# OutputModule.net
KiCad netlist of a schematic drawn in Altium Designer
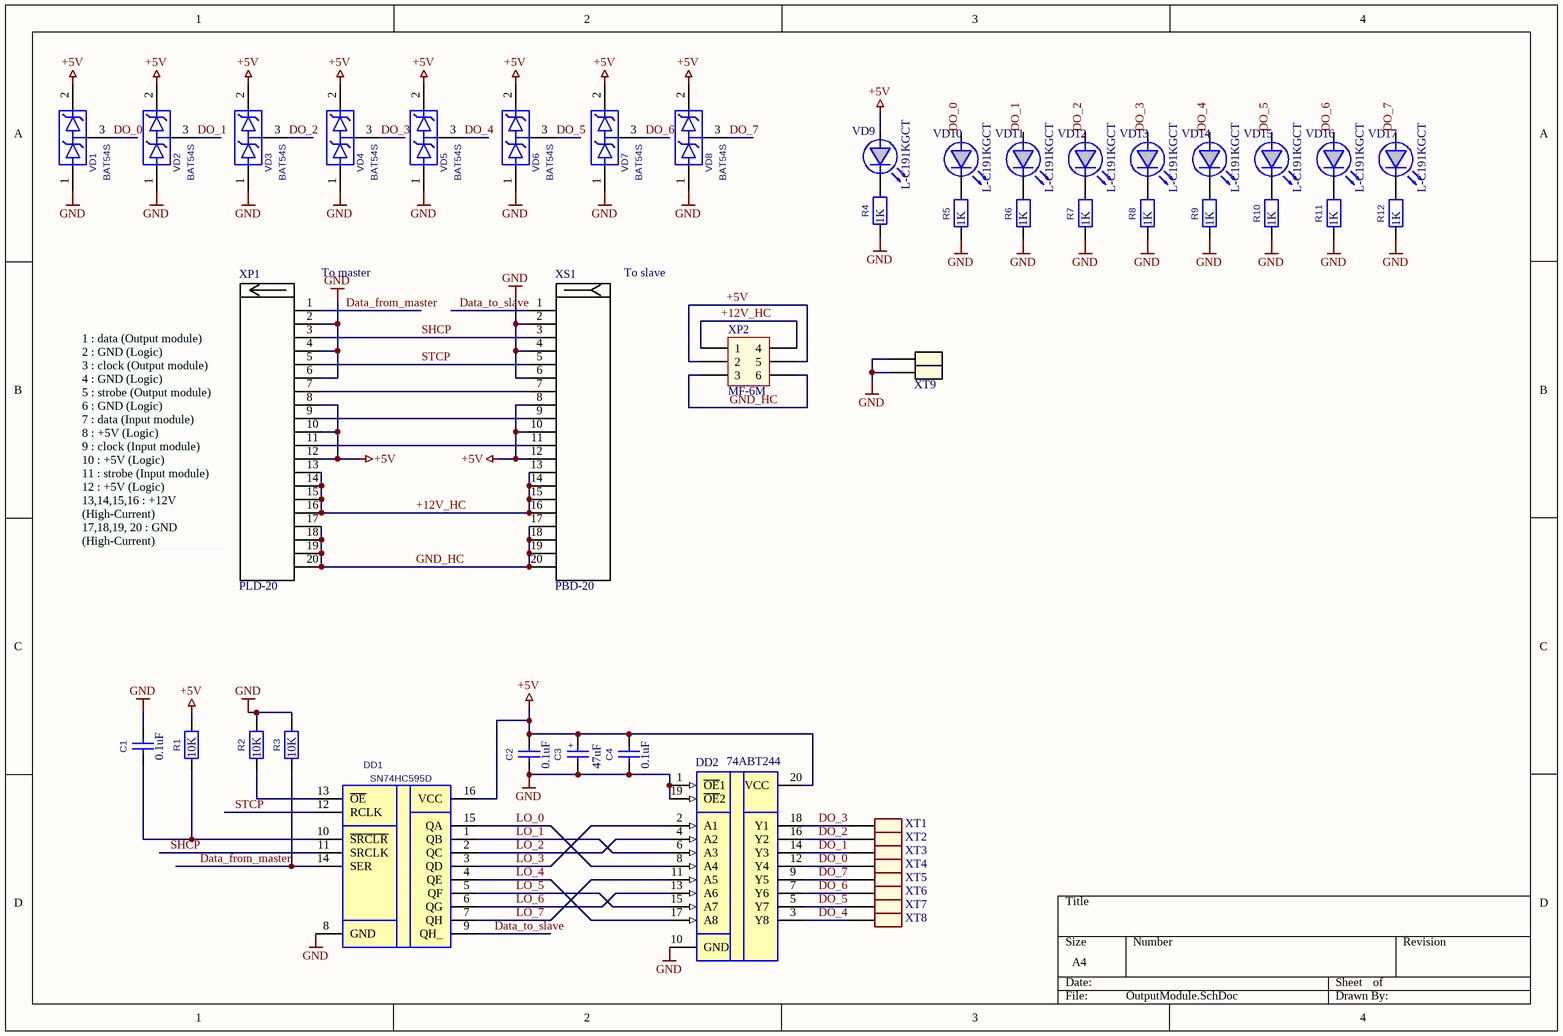
[diagram p0: OutputModule.SchDoc]

(export (version "E")
  (design (tool "Eeschema 10.0.6"))
  (components
    (comp (ref "C1")
      (value "0.1uF")
      (footprint "C-1608[0603]")
      (description "C-0603")
      (libsource (lib "Altium-RC") (part "C-0603"))
    )
    (comp (ref "C2")
      (value "0.1uF")
      (footprint "C-1608[0603]")
      (description "C-0603")
      (libsource (lib "Altium-RC") (part "C-0603"))
    )
    (comp (ref "C3")
      (value "47uF")
      (footprint "C-CASE")
      (description "C-CCASE")
      (libsource (lib "Altium-RC") (part "C-CCASE"))
    )
    (comp (ref "C4")
      (value "0.1uF")
      (footprint "C-1608[0603]")
      (description "C-0603")
      (libsource (lib "Altium-RC") (part "C-0603"))
    )
    (comp (ref "DD1")
      (value "SN74HC595D")
      (footprint "SO-G16")
      (libsource (lib "Altium-IC") (part "SN74HC595D"))
    )
    (comp (ref "DD2")
      (value "74ABT244")
      (footprint "TSSOP20")
      (description "Octal Buffer/Driver with 3-State Outputs")
      (libsource (lib "Altium-IC") (part "SN74LVC244APW"))
    )
    (comp (ref "R1")
      (value "10K")
      (footprint "R-1608[0603]")
      (description "R-0603")
      (libsource (lib "Altium-RC") (part "R-0603"))
    )
    (comp (ref "R2")
      (value "10K")
      (footprint "R-1608[0603]")
      (description "R-0603")
      (libsource (lib "Altium-RC") (part "R-0603"))
    )
    (comp (ref "R3")
      (value "10K")
      (footprint "R-1608[0603]")
      (description "R-0603")
      (libsource (lib "Altium-RC") (part "R-0603"))
    )
    (comp (ref "R4")
      (value "1K")
      (footprint "R-1608[0603]")
      (description "R-0603")
      (libsource (lib "Altium-RC") (part "R-0603"))
    )
    (comp (ref "R5")
      (value "1K")
      (footprint "R-1608[0603]")
      (description "R-0603")
      (libsource (lib "Altium-RC") (part "R-0603"))
    )
    (comp (ref "R6")
      (value "1K")
      (footprint "R-1608[0603]")
      (description "R-0603")
      (libsource (lib "Altium-RC") (part "R-0603"))
    )
    (comp (ref "R7")
      (value "1K")
      (footprint "R-1608[0603]")
      (description "R-0603")
      (libsource (lib "Altium-RC") (part "R-0603"))
    )
    (comp (ref "R8")
      (value "1K")
      (footprint "R-1608[0603]")
      (description "R-0603")
      (libsource (lib "Altium-RC") (part "R-0603"))
    )
    (comp (ref "R9")
      (value "1K")
      (footprint "R-1608[0603]")
      (description "R-0603")
      (libsource (lib "Altium-RC") (part "R-0603"))
    )
    (comp (ref "R10")
      (value "1K")
      (footprint "R-1608[0603]")
      (description "R-0603")
      (libsource (lib "Altium-RC") (part "R-0603"))
    )
    (comp (ref "R11")
      (value "1K")
      (footprint "R-1608[0603]")
      (description "R-0603")
      (libsource (lib "Altium-RC") (part "R-0603"))
    )
    (comp (ref "R12")
      (value "1K")
      (footprint "R-1608[0603]")
      (description "R-0603")
      (libsource (lib "Altium-RC") (part "R-0603"))
    )
    (comp (ref "VD1")
      (value "BAT54S")
      (footprint "SOT-23")
      (description "Schottky barrier (double) diodes")
      (libsource (lib "Altium-RECT") (part "BAT54S"))
    )
    (comp (ref "VD2")
      (value "BAT54S")
      (footprint "SOT-23")
      (description "Schottky barrier (double) diodes")
      (libsource (lib "Altium-RECT") (part "BAT54S"))
    )
    (comp (ref "VD3")
      (value "BAT54S")
      (footprint "SOT-23")
      (description "Schottky barrier (double) diodes")
      (libsource (lib "Altium-RECT") (part "BAT54S"))
    )
    (comp (ref "VD4")
      (value "BAT54S")
      (footprint "SOT-23")
      (description "Schottky barrier (double) diodes")
      (libsource (lib "Altium-RECT") (part "BAT54S"))
    )
    (comp (ref "VD5")
      (value "BAT54S")
      (footprint "SOT-23")
      (description "Schottky barrier (double) diodes")
      (libsource (lib "Altium-RECT") (part "BAT54S"))
    )
    (comp (ref "VD6")
      (value "BAT54S")
      (footprint "SOT-23")
      (description "Schottky barrier (double) diodes")
      (libsource (lib "Altium-RECT") (part "BAT54S"))
    )
    (comp (ref "VD7")
      (value "BAT54S")
      (footprint "SOT-23")
      (description "Schottky barrier (double) diodes")
      (libsource (lib "Altium-RECT") (part "BAT54S"))
    )
    (comp (ref "VD8")
      (value "BAT54S")
      (footprint "SOT-23")
      (description "Schottky barrier (double) diodes")
      (libsource (lib "Altium-RECT") (part "BAT54S"))
    )
    (comp (ref "VD9")
      (value "L-C191KGCT")
      (footprint "LED-0603")
      (description "0603 Green Led")
      (libsource (lib "Altium-OPTO") (part "L-C191KGCT"))
    )
    (comp (ref "VD10")
      (value "L-C191KGCT")
      (footprint "LED-0603")
      (description "0603 Green Led")
      (libsource (lib "Altium-OPTO") (part "L-C191KGCT"))
    )
    (comp (ref "VD11")
      (value "L-C191KGCT")
      (footprint "LED-0603")
      (description "0603 Green Led")
      (libsource (lib "Altium-OPTO") (part "L-C191KGCT"))
    )
    (comp (ref "VD12")
      (value "L-C191KGCT")
      (footprint "LED-0603")
      (description "0603 Green Led")
      (libsource (lib "Altium-OPTO") (part "L-C191KGCT"))
    )
    (comp (ref "VD13")
      (value "L-C191KGCT")
      (footprint "LED-0603")
      (description "0603 Green Led")
      (libsource (lib "Altium-OPTO") (part "L-C191KGCT"))
    )
    (comp (ref "VD14")
      (value "L-C191KGCT")
      (footprint "LED-0603")
      (description "0603 Green Led")
      (libsource (lib "Altium-OPTO") (part "L-C191KGCT"))
    )
    (comp (ref "VD15")
      (value "L-C191KGCT")
      (footprint "LED-0603")
      (description "0603 Green Led")
      (libsource (lib "Altium-OPTO") (part "L-C191KGCT"))
    )
    (comp (ref "VD16")
      (value "L-C191KGCT")
      (footprint "LED-0603")
      (description "0603 Green Led")
      (libsource (lib "Altium-OPTO") (part "L-C191KGCT"))
    )
    (comp (ref "VD17")
      (value "L-C191KGCT")
      (footprint "LED-0603")
      (description "0603 Green Led")
      (libsource (lib "Altium-OPTO") (part "L-C191KGCT"))
    )
    (comp (ref "XP1")
      (value "PLD-20")
      (footprint "PLD-20 ROT")
      (description "20 pin, 2 row, MALE connector")
      (libsource (lib "Altium-CONN") (part "PLD-20"))
    )
    (comp (ref "XP2")
      (value "MF-6M")
      (footprint "MF-6M")
      (description "Molex Male connector")
      (libsource (lib "Altium-CONN") (part "MF-6M"))
    )
    (comp (ref "XS1")
      (value "PBD-20")
      (footprint "PBD-20 Rot")
      (description "2.54mm, 20 pin FEMALE connector")
      (libsource (lib "Altium-CONN") (part "PBD-20"))
    )
    (comp (ref "XT1")
      (value "DG141V-01P")
      (footprint "DG141V-01P (XY123R)")
      (description "Клеммник нажимной 2.54мм")
      (libsource (lib "Altium-CONN") (part "DG141V-01P"))
    )
    (comp (ref "XT2")
      (value "DG141V-01P")
      (footprint "DG141V-01P (XY123R)")
      (description "Клеммник нажимной 2.54мм")
      (libsource (lib "Altium-CONN") (part "DG141V-01P"))
    )
    (comp (ref "XT3")
      (value "DG141V-01P")
      (footprint "DG141V-01P (XY123R)")
      (description "Клеммник нажимной 2.54мм")
      (libsource (lib "Altium-CONN") (part "DG141V-01P"))
    )
    (comp (ref "XT4")
      (value "DG141V-01P")
      (footprint "DG141V-01P (XY123R)")
      (description "Клеммник нажимной 2.54мм")
      (libsource (lib "Altium-CONN") (part "DG141V-01P"))
    )
    (comp (ref "XT5")
      (value "DG141V-01P")
      (footprint "DG141V-01P (XY123R)")
      (description "Клеммник нажимной 2.54мм")
      (libsource (lib "Altium-CONN") (part "DG141V-01P"))
    )
    (comp (ref "XT6")
      (value "DG141V-01P")
      (footprint "DG141V-01P (XY123R)")
      (description "Клеммник нажимной 2.54мм")
      (libsource (lib "Altium-CONN") (part "DG141V-01P"))
    )
    (comp (ref "XT7")
      (value "DG141V-01P")
      (footprint "DG141V-01P (XY123R)")
      (description "Клеммник нажимной 2.54мм")
      (libsource (lib "Altium-CONN") (part "DG141V-01P"))
    )
    (comp (ref "XT8")
      (value "DG141V-01P")
      (footprint "DG141V-01P (XY123R)")
      (description "Клеммник нажимной 2.54мм")
      (libsource (lib "Altium-CONN") (part "DG141V-01P"))
    )
    (comp (ref "XT9")
      (value "1-1776244-0 (TYCO)")
      (footprint "1-1776244-0")
      (description "Винтовой клеммник 5.0мм")
      (libsource (lib "Altium-CONN") (part "1-1776244-0 (TYCO)"))
    )
  )
  (nets
    (net (code "1") (name "+5V") (class "Default")
      (node (ref "C2") (pin "1") (pintype "passive"))
      (node (ref "C3") (pin "1") (pinfunction "+_1") (pintype "passive"))
      (node (ref "C4") (pin "1") (pintype "passive"))
      (node (ref "DD1") (pin "16") (pinfunction "VCC_16") (pintype "passive"))
      (node (ref "DD2") (pin "20") (pinfunction "VCC_20") (pintype "power_in"))
      (node (ref "R1") (pin "2") (pinfunction "2_2") (pintype "passive"))
      (node (ref "VD1") (pin "2") (pinfunction "c_2") (pintype "passive"))
      (node (ref "VD2") (pin "2") (pinfunction "c_2") (pintype "passive"))
      (node (ref "VD3") (pin "2") (pinfunction "c_2") (pintype "passive"))
      (node (ref "VD4") (pin "2") (pinfunction "c_2") (pintype "passive"))
      (node (ref "VD5") (pin "2") (pinfunction "c_2") (pintype "passive"))
      (node (ref "VD6") (pin "2") (pinfunction "c_2") (pintype "passive"))
      (node (ref "VD7") (pin "2") (pinfunction "c_2") (pintype "passive"))
      (node (ref "VD8") (pin "2") (pinfunction "c_2") (pintype "passive"))
      (node (ref "VD9") (pin "2") (pinfunction "A_2") (pintype "passive"))
      (node (ref "XP1") (pin "10") (pintype "passive"))
      (node (ref "XP1") (pin "12") (pintype "passive"))
      (node (ref "XP1") (pin "8") (pintype "passive"))
      (node (ref "XP2") (pin "2") (pinfunction "2_2") (pintype "passive"))
      (node (ref "XP2") (pin "5") (pinfunction "5_5") (pintype "passive"))
      (node (ref "XS1") (pin "10") (pintype "passive"))
      (node (ref "XS1") (pin "12") (pintype "passive"))
      (node (ref "XS1") (pin "8") (pintype "passive"))
    )
    (net (code "2") (name "/+12V_HC") (class "Default")
      (node (ref "XP1") (pin "13") (pintype "passive"))
      (node (ref "XP1") (pin "14") (pintype "passive"))
      (node (ref "XP1") (pin "15") (pintype "passive"))
      (node (ref "XP1") (pin "16") (pintype "passive"))
      (node (ref "XP2") (pin "1") (pinfunction "1_1") (pintype "passive"))
      (node (ref "XP2") (pin "4") (pinfunction "4_4") (pintype "passive"))
      (node (ref "XS1") (pin "13") (pintype "passive"))
      (node (ref "XS1") (pin "14") (pintype "passive"))
      (node (ref "XS1") (pin "15") (pintype "passive"))
      (node (ref "XS1") (pin "16") (pintype "passive"))
    )
    (net (code "3") (name "/DO_0") (class "Default")
      (node (ref "DD2") (pin "12") (pinfunction "Y4_12") (pintype "tri_state"))
      (node (ref "VD1") (pin "3") (pinfunction "ka_3") (pintype "passive"))
      (node (ref "VD10") (pin "2") (pinfunction "A_2") (pintype "passive"))
      (node (ref "XT4") (pin "1") (pintype "passive"))
    )
    (net (code "4") (name "/DO_1") (class "Default")
      (node (ref "DD2") (pin "14") (pinfunction "Y3_14") (pintype "tri_state"))
      (node (ref "VD11") (pin "2") (pinfunction "A_2") (pintype "passive"))
      (node (ref "VD2") (pin "3") (pinfunction "ka_3") (pintype "passive"))
      (node (ref "XT3") (pin "1") (pintype "passive"))
    )
    (net (code "5") (name "/DO_2") (class "Default")
      (node (ref "DD2") (pin "16") (pinfunction "Y2_16") (pintype "tri_state"))
      (node (ref "VD12") (pin "2") (pinfunction "A_2") (pintype "passive"))
      (node (ref "VD3") (pin "3") (pinfunction "ka_3") (pintype "passive"))
      (node (ref "XT2") (pin "1") (pintype "passive"))
    )
    (net (code "6") (name "/DO_3") (class "Default")
      (node (ref "DD2") (pin "18") (pinfunction "Y1_18") (pintype "tri_state"))
      (node (ref "VD13") (pin "2") (pinfunction "A_2") (pintype "passive"))
      (node (ref "VD4") (pin "3") (pinfunction "ka_3") (pintype "passive"))
      (node (ref "XT1") (pin "1") (pintype "passive"))
    )
    (net (code "7") (name "/DO_4") (class "Default")
      (node (ref "DD2") (pin "3") (pinfunction "Y8_3") (pintype "tri_state"))
      (node (ref "VD14") (pin "2") (pinfunction "A_2") (pintype "passive"))
      (node (ref "VD5") (pin "3") (pinfunction "ka_3") (pintype "passive"))
      (node (ref "XT8") (pin "1") (pintype "passive"))
    )
    (net (code "8") (name "/DO_5") (class "Default")
      (node (ref "DD2") (pin "5") (pinfunction "Y7_5") (pintype "tri_state"))
      (node (ref "VD15") (pin "2") (pinfunction "A_2") (pintype "passive"))
      (node (ref "VD6") (pin "3") (pinfunction "ka_3") (pintype "passive"))
      (node (ref "XT7") (pin "1") (pintype "passive"))
    )
    (net (code "9") (name "/DO_6") (class "Default")
      (node (ref "DD2") (pin "7") (pinfunction "Y6_7") (pintype "tri_state"))
      (node (ref "VD16") (pin "2") (pinfunction "A_2") (pintype "passive"))
      (node (ref "VD7") (pin "3") (pinfunction "ka_3") (pintype "passive"))
      (node (ref "XT6") (pin "1") (pintype "passive"))
    )
    (net (code "10") (name "/DO_7") (class "Default")
      (node (ref "DD2") (pin "9") (pinfunction "Y5_9") (pintype "tri_state"))
      (node (ref "VD17") (pin "2") (pinfunction "A_2") (pintype "passive"))
      (node (ref "VD8") (pin "3") (pinfunction "ka_3") (pintype "passive"))
      (node (ref "XT5") (pin "1") (pintype "passive"))
    )
    (net (code "11") (name "/Data_from_master") (class "Default")
      (node (ref "DD1") (pin "14") (pinfunction "SER_14") (pintype "passive"))
      (node (ref "R3") (pin "1") (pinfunction "1_1") (pintype "passive"))
      (node (ref "XP1") (pin "1") (pintype "passive"))
    )
    (net (code "12") (name "/Data_to_slave") (class "Default")
      (node (ref "DD1") (pin "9") (pinfunction "QH__9") (pintype "passive"))
      (node (ref "XS1") (pin "1") (pintype "passive"))
    )
    (net (code "13") (name "/GND_HC") (class "Default")
      (node (ref "XP1") (pin "17") (pintype "passive"))
      (node (ref "XP1") (pin "18") (pintype "passive"))
      (node (ref "XP1") (pin "19") (pintype "passive"))
      (node (ref "XP1") (pin "20") (pintype "passive"))
      (node (ref "XP2") (pin "3") (pinfunction "3_3") (pintype "passive"))
      (node (ref "XP2") (pin "6") (pinfunction "6_6") (pintype "passive"))
      (node (ref "XS1") (pin "17") (pintype "passive"))
      (node (ref "XS1") (pin "18") (pintype "passive"))
      (node (ref "XS1") (pin "19") (pintype "passive"))
      (node (ref "XS1") (pin "20") (pintype "passive"))
    )
    (net (code "14") (name "/LO_0") (class "Default")
      (node (ref "DD1") (pin "15") (pinfunction "QA_15") (pintype "passive"))
      (node (ref "DD2") (pin "8") (pinfunction "A4_8") (pintype "input"))
    )
    (net (code "15") (name "/LO_1") (class "Default")
      (node (ref "DD1") (pin "1") (pinfunction "QB_1") (pintype "passive"))
      (node (ref "DD2") (pin "6") (pinfunction "A3_6") (pintype "input"))
    )
    (net (code "16") (name "/LO_2") (class "Default")
      (node (ref "DD1") (pin "2") (pinfunction "QC_2") (pintype "passive"))
      (node (ref "DD2") (pin "4") (pinfunction "A2_4") (pintype "input"))
    )
    (net (code "17") (name "/LO_3") (class "Default")
      (node (ref "DD1") (pin "3") (pinfunction "QD_3") (pintype "passive"))
      (node (ref "DD2") (pin "2") (pinfunction "A1_2") (pintype "input"))
    )
    (net (code "18") (name "/LO_4") (class "Default")
      (node (ref "DD1") (pin "4") (pinfunction "QE_4") (pintype "passive"))
      (node (ref "DD2") (pin "17") (pinfunction "A8_17") (pintype "input"))
    )
    (net (code "19") (name "/LO_5") (class "Default")
      (node (ref "DD1") (pin "5") (pinfunction "QF_5") (pintype "passive"))
      (node (ref "DD2") (pin "15") (pinfunction "A7_15") (pintype "input"))
    )
    (net (code "20") (name "/LO_6") (class "Default")
      (node (ref "DD1") (pin "6") (pinfunction "QG_6") (pintype "passive"))
      (node (ref "DD2") (pin "13") (pinfunction "A6_13") (pintype "input"))
    )
    (net (code "21") (name "/LO_7") (class "Default")
      (node (ref "DD1") (pin "7") (pinfunction "QH_7") (pintype "passive"))
      (node (ref "DD2") (pin "11") (pinfunction "A5_11") (pintype "input"))
    )
    (net (code "22") (name "/SHCP") (class "Default")
      (node (ref "DD1") (pin "11") (pinfunction "SRCLK_11") (pintype "passive"))
      (node (ref "XP1") (pin "3") (pintype "passive"))
      (node (ref "XS1") (pin "3") (pintype "passive"))
    )
    (net (code "23") (name "/STCP") (class "Default")
      (node (ref "DD1") (pin "12") (pinfunction "RCLK_12") (pintype "passive"))
      (node (ref "XP1") (pin "5") (pintype "passive"))
      (node (ref "XS1") (pin "5") (pintype "passive"))
    )
    (net (code "24") (name "GND") (class "Default")
      (node (ref "C1") (pin "1") (pintype "passive"))
      (node (ref "C2") (pin "2") (pintype "passive"))
      (node (ref "C3") (pin "2") (pinfunction "-_2") (pintype "passive"))
      (node (ref "C4") (pin "2") (pintype "passive"))
      (node (ref "DD1") (pin "8") (pinfunction "GND_8") (pintype "passive"))
      (node (ref "DD2") (pin "1") (pinfunction "~{OE}1_1") (pintype "input"))
      (node (ref "DD2") (pin "10") (pinfunction "GND_10") (pintype "power_in"))
      (node (ref "DD2") (pin "19") (pinfunction "~{OE}2_19") (pintype "input"))
      (node (ref "R10") (pin "1") (pinfunction "1_1") (pintype "passive"))
      (node (ref "R11") (pin "1") (pinfunction "1_1") (pintype "passive"))
      (node (ref "R12") (pin "1") (pinfunction "1_1") (pintype "passive"))
      (node (ref "R2") (pin "2") (pinfunction "2_2") (pintype "passive"))
      (node (ref "R3") (pin "2") (pinfunction "2_2") (pintype "passive"))
      (node (ref "R4") (pin "1") (pinfunction "1_1") (pintype "passive"))
      (node (ref "R5") (pin "1") (pinfunction "1_1") (pintype "passive"))
      (node (ref "R6") (pin "1") (pinfunction "1_1") (pintype "passive"))
      (node (ref "R7") (pin "1") (pinfunction "1_1") (pintype "passive"))
      (node (ref "R8") (pin "1") (pinfunction "1_1") (pintype "passive"))
      (node (ref "R9") (pin "1") (pinfunction "1_1") (pintype "passive"))
      (node (ref "VD1") (pin "1") (pinfunction "a_1") (pintype "passive"))
      (node (ref "VD2") (pin "1") (pinfunction "a_1") (pintype "passive"))
      (node (ref "VD3") (pin "1") (pinfunction "a_1") (pintype "passive"))
      (node (ref "VD4") (pin "1") (pinfunction "a_1") (pintype "passive"))
      (node (ref "VD5") (pin "1") (pinfunction "a_1") (pintype "passive"))
      (node (ref "VD6") (pin "1") (pinfunction "a_1") (pintype "passive"))
      (node (ref "VD7") (pin "1") (pinfunction "a_1") (pintype "passive"))
      (node (ref "VD8") (pin "1") (pinfunction "a_1") (pintype "passive"))
      (node (ref "XP1") (pin "2") (pintype "passive"))
      (node (ref "XP1") (pin "4") (pintype "passive"))
      (node (ref "XP1") (pin "6") (pintype "passive"))
      (node (ref "XS1") (pin "2") (pintype "passive"))
      (node (ref "XS1") (pin "4") (pintype "passive"))
      (node (ref "XS1") (pin "6") (pintype "passive"))
      (node (ref "XT9") (pin "1") (pintype "passive"))
      (node (ref "XT9") (pin "2") (pintype "passive"))
    )
    (net (code "25") (name "Net-(DD1-~{OE})") (class "Default")
      (node (ref "DD1") (pin "13") (pinfunction "~{OE}_13") (pintype "passive"))
      (node (ref "R2") (pin "1") (pinfunction "1_1") (pintype "passive"))
    )
    (net (code "26") (name "Net-(DD1-~{SRCLR})") (class "Default")
      (node (ref "C1") (pin "2") (pintype "passive"))
      (node (ref "DD1") (pin "10") (pinfunction "~{SRCLR}_10") (pintype "passive"))
      (node (ref "R1") (pin "1") (pinfunction "1_1") (pintype "passive"))
    )
    (net (code "27") (name "Net-(VD9-K)") (class "Default")
      (node (ref "R4") (pin "2") (pinfunction "2_2") (pintype "passive"))
      (node (ref "VD9") (pin "1") (pinfunction "K_1") (pintype "passive"))
    )
    (net (code "28") (name "Net-(VD10-K)") (class "Default")
      (node (ref "R5") (pin "2") (pinfunction "2_2") (pintype "passive"))
      (node (ref "VD10") (pin "1") (pinfunction "K_1") (pintype "passive"))
    )
    (net (code "29") (name "Net-(VD11-K)") (class "Default")
      (node (ref "R6") (pin "2") (pinfunction "2_2") (pintype "passive"))
      (node (ref "VD11") (pin "1") (pinfunction "K_1") (pintype "passive"))
    )
    (net (code "30") (name "Net-(VD12-K)") (class "Default")
      (node (ref "R7") (pin "2") (pinfunction "2_2") (pintype "passive"))
      (node (ref "VD12") (pin "1") (pinfunction "K_1") (pintype "passive"))
    )
    (net (code "31") (name "Net-(VD13-K)") (class "Default")
      (node (ref "R8") (pin "2") (pinfunction "2_2") (pintype "passive"))
      (node (ref "VD13") (pin "1") (pinfunction "K_1") (pintype "passive"))
    )
    (net (code "32") (name "Net-(VD14-K)") (class "Default")
      (node (ref "R9") (pin "2") (pinfunction "2_2") (pintype "passive"))
      (node (ref "VD14") (pin "1") (pinfunction "K_1") (pintype "passive"))
    )
    (net (code "33") (name "Net-(VD15-K)") (class "Default")
      (node (ref "R10") (pin "2") (pinfunction "2_2") (pintype "passive"))
      (node (ref "VD15") (pin "1") (pinfunction "K_1") (pintype "passive"))
    )
    (net (code "34") (name "Net-(VD16-K)") (class "Default")
      (node (ref "R11") (pin "2") (pinfunction "2_2") (pintype "passive"))
      (node (ref "VD16") (pin "1") (pinfunction "K_1") (pintype "passive"))
    )
    (net (code "35") (name "Net-(VD17-K)") (class "Default")
      (node (ref "R12") (pin "2") (pinfunction "2_2") (pintype "passive"))
      (node (ref "VD17") (pin "1") (pinfunction "K_1") (pintype "passive"))
    )
    (net (code "36") (name "Net-(XP1-Pad7)") (class "Default")
      (node (ref "XP1") (pin "7") (pintype "passive"))
      (node (ref "XS1") (pin "7") (pintype "passive"))
    )
    (net (code "37") (name "Net-(XP1-Pad9)") (class "Default")
      (node (ref "XP1") (pin "9") (pintype "passive"))
      (node (ref "XS1") (pin "9") (pintype "passive"))
    )
    (net (code "38") (name "Net-(XP1-Pad11)") (class "Default")
      (node (ref "XP1") (pin "11") (pintype "passive"))
      (node (ref "XS1") (pin "11") (pintype "passive"))
    )
  )
)
